# TPDH-Walrus.net
KiCad netlist of a schematic drawn in EAGLE
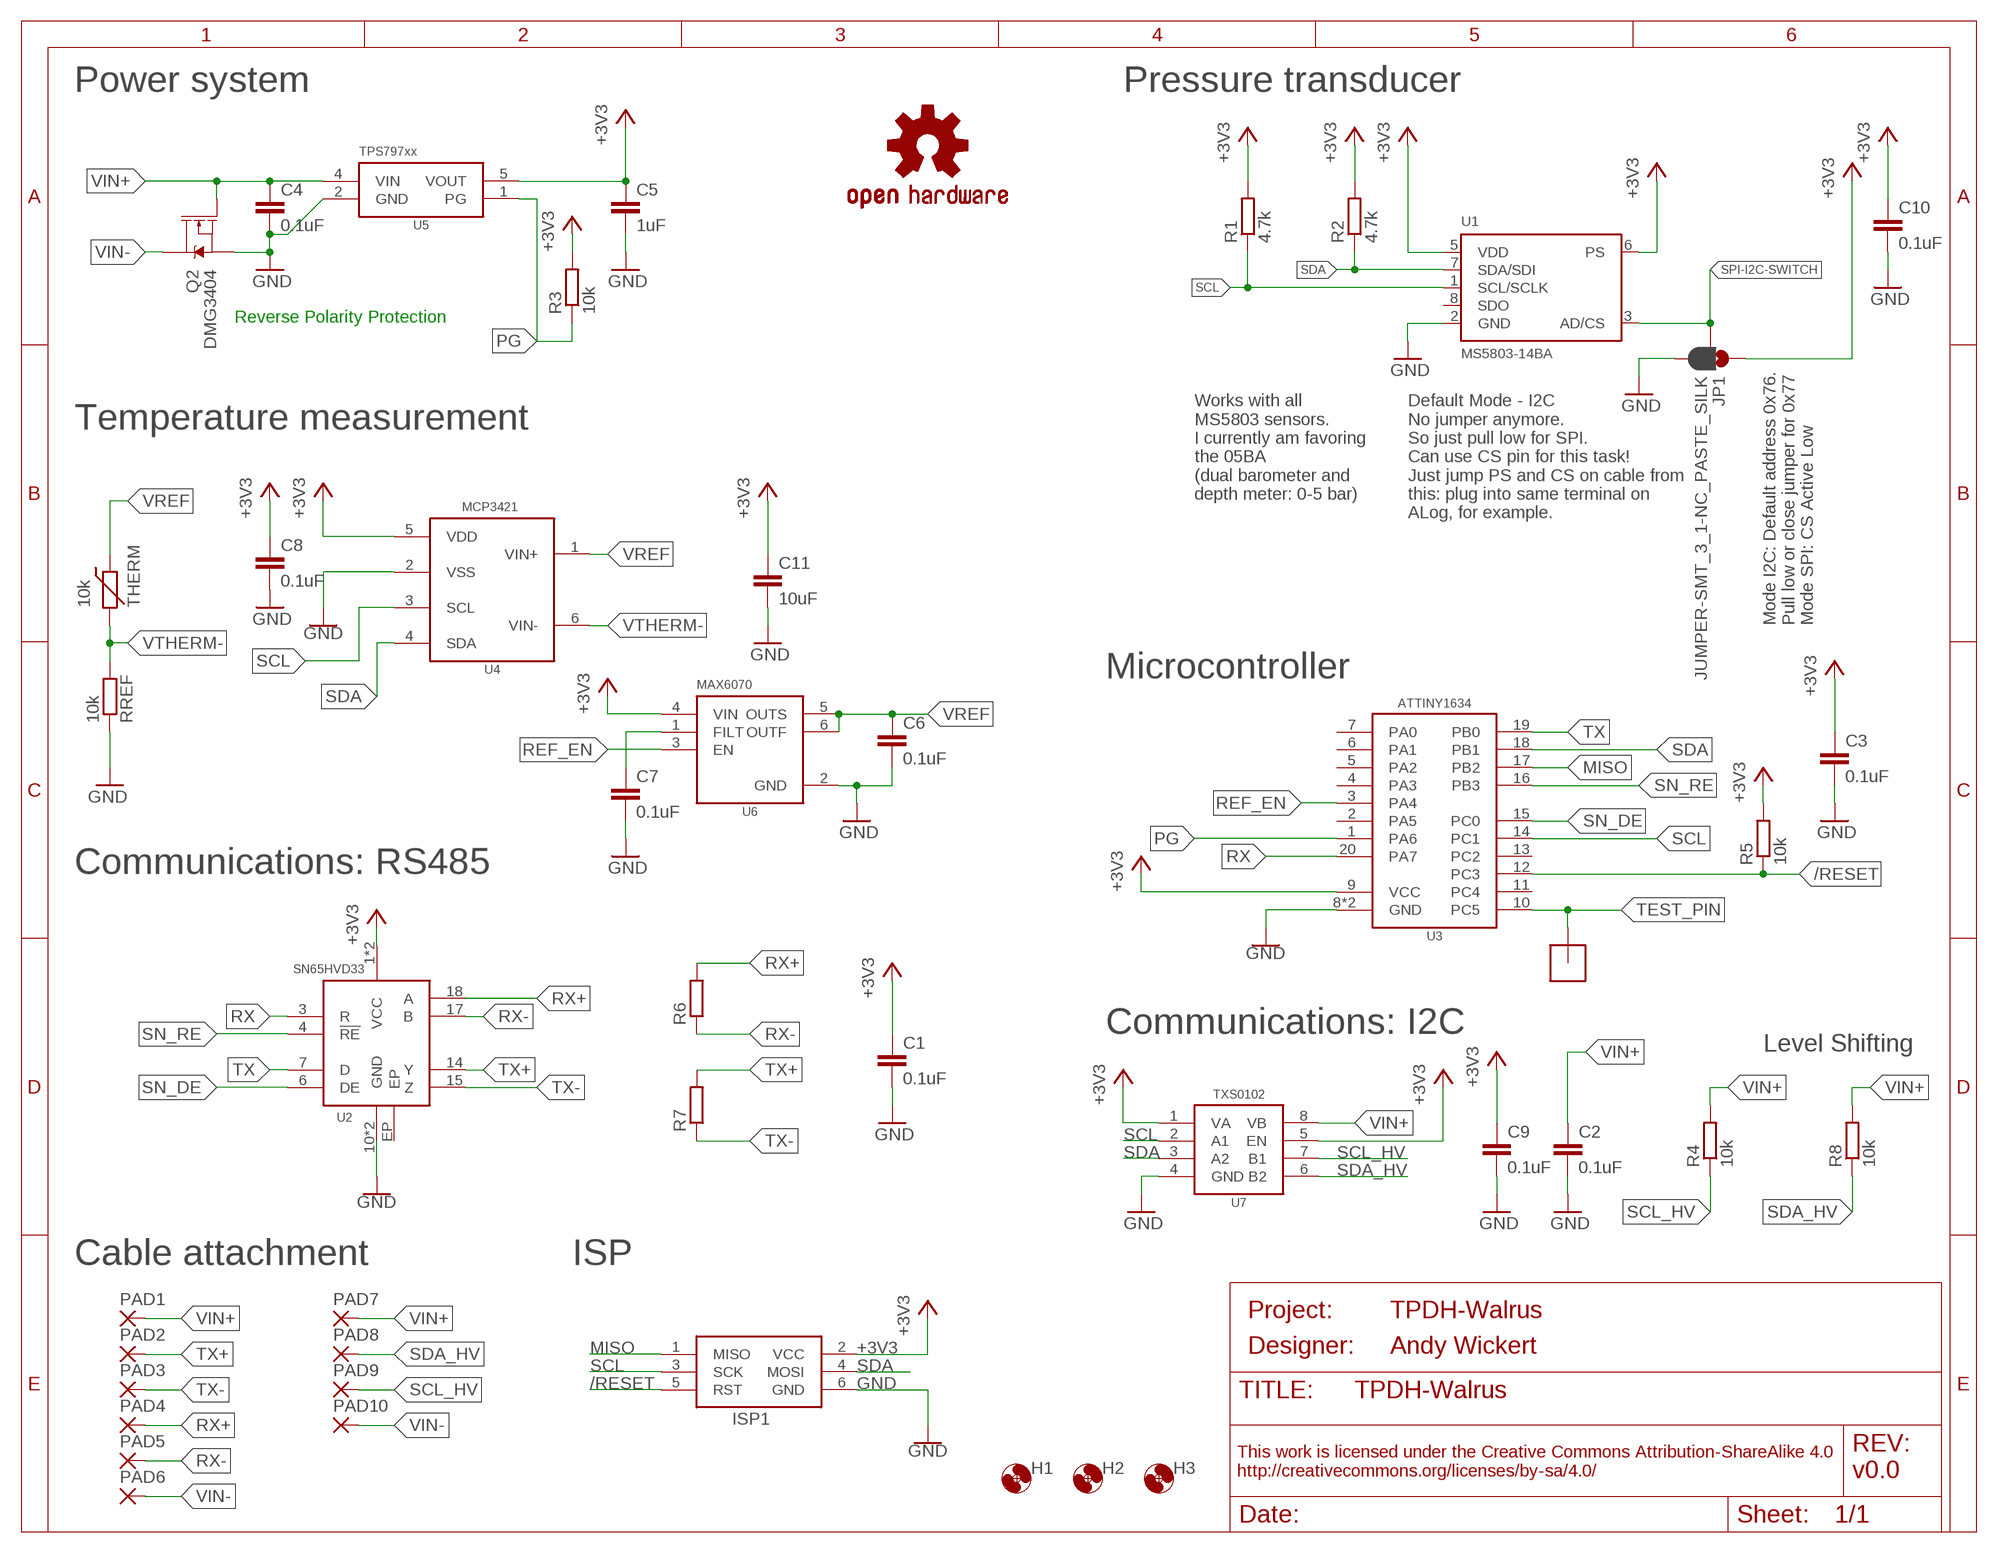
[diagram p0: schematic, sheet 1]

(export (version "E")
  (design (tool "Eeschema 10.0.6"))
  (components
    (comp (ref "C1")
      (value "0.1uF")
      (footprint "eagle-import:C0402")
      (fields (field (name "MF") "Murata") (field (name "MPN") "GCM155R71C104KA55D"))
      (libsource (lib "eagle-import") (part "C-EUC04020.1UF"))
    )
    (comp (ref "C2")
      (value "0.1uF")
      (footprint "eagle-import:C0402")
      (fields (field (name "MF") "Murata") (field (name "MPN") "GCM155R71C104KA55D"))
      (libsource (lib "eagle-import") (part "C-EUC04020.1UF"))
    )
    (comp (ref "C3")
      (value "0.1uF")
      (footprint "eagle-import:C0402")
      (fields (field (name "MF") "Murata") (field (name "MPN") "GCM155R71C104KA55D"))
      (libsource (lib "eagle-import") (part "C-EUC04020.1UF"))
    )
    (comp (ref "C4")
      (value "0.1uF")
      (footprint "eagle-import:C0402")
      (fields (field (name "MF") "Murata") (field (name "MPN") "GCM155R71C104KA55D"))
      (libsource (lib "eagle-import") (part "C-EUC04020.1UF"))
    )
    (comp (ref "C5")
      (value "1uF")
      (footprint "eagle-import:C0603")
      (fields (field (name "MF") "Murata") (field (name "MPN") "GRM188R61C105KA12D"))
      (libsource (lib "eagle-import") (part "C-EUC06031UF"))
    )
    (comp (ref "C6")
      (value "0.1uF")
      (footprint "eagle-import:C0402")
      (fields (field (name "MF") "Murata") (field (name "MPN") "GCM155R71C104KA55D"))
      (libsource (lib "eagle-import") (part "C-EUC04020.1UF"))
    )
    (comp (ref "C7")
      (value "0.1uF")
      (footprint "eagle-import:C0402")
      (fields (field (name "MF") "Murata") (field (name "MPN") "GCM155R71C104KA55D"))
      (libsource (lib "eagle-import") (part "C-EUC04020.1UF"))
    )
    (comp (ref "C8")
      (value "0.1uF")
      (footprint "eagle-import:C0402")
      (fields (field (name "MF") "Murata") (field (name "MPN") "GCM155R71C104KA55D"))
      (libsource (lib "eagle-import") (part "C-EUC04020.1UF"))
    )
    (comp (ref "C9")
      (value "0.1uF")
      (footprint "eagle-import:C0402")
      (fields (field (name "MF") "Murata") (field (name "MPN") "GCM155R71C104KA55D"))
      (libsource (lib "eagle-import") (part "C-EUC04020.1UF"))
    )
    (comp (ref "C10")
      (value "0.1uF")
      (footprint "eagle-import:C0402")
      (fields (field (name "MF") "Murata") (field (name "MPN") "GCM155R71C104KA55D"))
      (libsource (lib "eagle-import") (part "C-EUC04020.1UF"))
    )
    (comp (ref "C11")
      (value "10uF")
      (footprint "eagle-import:C0805")
      (fields (field (name "MF") "Murata") (field (name "MPN") "GRM21BR61C106KE15K"))
      (libsource (lib "eagle-import") (part "C-EUC080510UF"))
    )
    (comp (ref "H1")
      (value "MOUNTING_HOLE2_NP")
      (footprint "eagle-import:2_56")
      (libsource (lib "eagle-import") (part "MOUNTING_HOLE2_NP"))
    )
    (comp (ref "H2")
      (value "MOUNTING_HOLE2_NP")
      (footprint "eagle-import:2_56")
      (libsource (lib "eagle-import") (part "MOUNTING_HOLE2_NP"))
    )
    (comp (ref "H3")
      (value "MOUNTING_HOLE2_NP")
      (footprint "eagle-import:2_56")
      (libsource (lib "eagle-import") (part "MOUNTING_HOLE2_NP"))
    )
    (comp (ref "ISP1")
      (value "AVRISP-6")
      (footprint "eagle-import:AVRISP")
      (libsource (lib "eagle-import") (part "AVRISP-6"))
    )
    (comp (ref "JP1")
      (value "JUMPER-SMT_3_1-NC_PASTE_SILK")
      (footprint "eagle-import:SMT-JUMPER_3_1-NC_PASTE_SILK")
      (libsource (lib "eagle-import") (part "JUMPER-SMT_3_1-NC_PASTE_SILK"))
    )
    (comp (ref "LOGO1")
      (value "OSHW-LOGOM")
      (footprint "eagle-import:OSHW-LOGO-M")
      (libsource (lib "eagle-import") (part "OSHW-LOGOM"))
    )
    (comp (ref "PAD1")
      (value "2,15/1,0")
      (footprint "eagle-import:2,15_1,0")
      (libsource (lib "eagle-import") (part "2,15/1,0"))
    )
    (comp (ref "PAD2")
      (value "2,15/1,0")
      (footprint "eagle-import:2,15_1,0")
      (libsource (lib "eagle-import") (part "2,15/1,0"))
    )
    (comp (ref "PAD3")
      (value "2,15/1,0")
      (footprint "eagle-import:2,15_1,0")
      (libsource (lib "eagle-import") (part "2,15/1,0"))
    )
    (comp (ref "PAD4")
      (value "2,15/1,0")
      (footprint "eagle-import:2,15_1,0")
      (libsource (lib "eagle-import") (part "2,15/1,0"))
    )
    (comp (ref "PAD5")
      (value "2,15/1,0")
      (footprint "eagle-import:2,15_1,0")
      (libsource (lib "eagle-import") (part "2,15/1,0"))
    )
    (comp (ref "PAD6")
      (value "2,15/1,0")
      (footprint "eagle-import:2,15_1,0")
      (libsource (lib "eagle-import") (part "2,15/1,0"))
    )
    (comp (ref "PAD7")
      (value "2,15/1,0")
      (footprint "eagle-import:2,15_1,0")
      (libsource (lib "eagle-import") (part "2,15/1,0"))
    )
    (comp (ref "PAD8")
      (value "2,15/1,0")
      (footprint "eagle-import:2,15_1,0")
      (libsource (lib "eagle-import") (part "2,15/1,0"))
    )
    (comp (ref "PAD9")
      (value "2,15/1,0")
      (footprint "eagle-import:2,15_1,0")
      (libsource (lib "eagle-import") (part "2,15/1,0"))
    )
    (comp (ref "PAD10")
      (value "2,15/1,0")
      (footprint "eagle-import:2,15_1,0")
      (libsource (lib "eagle-import") (part "2,15/1,0"))
    )
    (comp (ref "Q2")
      (value "DMG3404")
      (footprint "eagle-import:SOT23-3")
      (fields (field (name "MF") "Diodes Incorporated") (field (name "MPN") "DMG3404L-7"))
      (libsource (lib "eagle-import") (part "MOSFET-NCH-DMG3404L"))
    )
    (comp (ref "R1")
      (value "4.7k")
      (footprint "eagle-import:R0402")
      (fields (field (name "MF") "Yageo") (field (name "MPN") "RC0402JR-074K7L"))
      (libsource (lib "eagle-import") (part "R-EU_R04024.7K"))
    )
    (comp (ref "R2")
      (value "4.7k")
      (footprint "eagle-import:R0402")
      (fields (field (name "MF") "Yageo") (field (name "MPN") "RC0402JR-074K7L"))
      (libsource (lib "eagle-import") (part "R-EU_R04024.7K"))
    )
    (comp (ref "R3")
      (value "10k")
      (footprint "eagle-import:R0402")
      (fields (field (name "MF") "Yageo") (field (name "MPN") "RC0603FR-0710KL"))
      (libsource (lib "eagle-import") (part "R-EU_R040210K"))
    )
    (comp (ref "R4")
      (value "10k")
      (footprint "eagle-import:R0402")
      (fields (field (name "MF") "Yageo") (field (name "MPN") "RC0603FR-0710KL"))
      (libsource (lib "eagle-import") (part "R-EU_R040210K"))
    )
    (comp (ref "R5")
      (value "10k")
      (footprint "eagle-import:R0402")
      (fields (field (name "MF") "Yageo") (field (name "MPN") "RC0603FR-0710KL"))
      (libsource (lib "eagle-import") (part "R-EU_R040210K"))
    )
    (comp (ref "R6")
      (value "R-EU_100R0402")
      (footprint "eagle-import:R0402")
      (fields
        (field (name "MF") "Yageo")
        (field (name "MPN") "RC0402FR-07100RL")
        (field (name "VALUE_PART") "100")
      )
      (libsource (lib "eagle-import") (part "R-EU_R0402100"))
    )
    (comp (ref "R7")
      (value "R-EU_100R0402")
      (footprint "eagle-import:R0402")
      (fields
        (field (name "MF") "Yageo")
        (field (name "MPN") "RC0402FR-07100RL")
        (field (name "VALUE_PART") "100")
      )
      (libsource (lib "eagle-import") (part "R-EU_R0402100"))
    )
    (comp (ref "R8")
      (value "10k")
      (footprint "eagle-import:R0402")
      (fields (field (name "MF") "Yageo") (field (name "MPN") "RC0603FR-0710KL"))
      (libsource (lib "eagle-import") (part "R-EU_R040210K"))
    )
    (comp (ref "RREF")
      (value "10k")
      (footprint "eagle-import:R0603")
      (fields
        (field (name "MF") "Panasonic")
        (field (name "MPN") "ERA-3AEB103V")
        (field (name "DIGIKEY") "P10KDBCT-ND")
        (field (name "MF_1") "Panasonic")
        (field (name "MPN_1") "ERA-3AEB103V")
      )
      (libsource (lib "eagle-import") (part "R-EU_R0603P10K"))
    )
    (comp (ref "THERM")
      (value "10k")
      (footprint "eagle-import:R0603")
      (fields
        (field (name "MF") "Murata")
        (field (name "MPN") "NCU18XH103F60RB")
        (field (name "MF_1") "Murata")
      )
      (libsource (lib "eagle-import") (part "THERMISTOR10K"))
    )
    (comp (ref "U$12")
      (value "POGO_PAD")
      (footprint "eagle-import:POGO_PAD")
      (libsource (lib "eagle-import") (part "POGO_PAD"))
    )
    (comp (ref "U1")
      (value "MS5803-14BA")
      (footprint "eagle-import:MS5803")
      (fields (field (name "MF") "TE") (field (name "MPN") "MS580305BA01-00"))
      (libsource (lib "eagle-import") (part "MS5803-14BA"))
    )
    (comp (ref "U2")
      (value "SN65HVD33RHL")
      (footprint "eagle-import:VQFN-20_POWER")
      (fields (field (name "MF") "TI") (field (name "MPN") "SN65HVD33RHLR"))
      (libsource (lib "eagle-import") (part "SN65HVD33RHL"))
    )
    (comp (ref "U3")
      (value "ATTINY1634QFN")
      (footprint "eagle-import:QFN20")
      (fields (field (name "MF") "Atmel") (field (name "MPN") "ATTINY1634-MUR"))
      (libsource (lib "eagle-import") (part "ATTINY1634QFN"))
    )
    (comp (ref "U4")
      (value "MCP3421A3")
      (footprint "eagle-import:SOT23-6L")
      (fields
        (field (name "DISP") "MCP3421")
        (field (name "MF") "Microchip")
        (field (name "MPN") "MCP3421A3T-E/CH")
      )
      (libsource (lib "eagle-import") (part "MCP3421A3"))
    )
    (comp (ref "U5")
      (value "TPS79733")
      (footprint "eagle-import:DCK_R-PDSO-G5")
      (fields (field (name "MF") "TI") (field (name "MPN") "TPS79733DCKR"))
      (libsource (lib "eagle-import") (part "TPS79733"))
    )
    (comp (ref "U6")
      (value "MAX6070AAUT18")
      (footprint "eagle-import:SOT23-6L")
      (fields (field (name "MF") "Maxim") (field (name "MPN") "MAX6070BAUT18+T"))
      (libsource (lib "eagle-import") (part "MAX6070AAUT18"))
    )
    (comp (ref "U7")
      (value "TXS0102DQM")
      (footprint "eagle-import:DQM_R-PX2SON-N8")
      (fields (field (name "MF") "TI") (field (name "MPN") "TXS0102DQMR"))
      (libsource (lib "eagle-import") (part "TXS0102DQM"))
    )
  )
  (nets
    (net (code "1") (name "+3V3") (class "Default")
      (node (ref "C1") (pin "1") (pinfunction "1_1") (pintype "passive"))
      (node (ref "C10") (pin "1") (pinfunction "1_1") (pintype "passive"))
      (node (ref "C11") (pin "1") (pinfunction "1_1") (pintype "passive"))
      (node (ref "C3") (pin "1") (pinfunction "1_1") (pintype "passive"))
      (node (ref "C5") (pin "1") (pinfunction "1_1") (pintype "passive"))
      (node (ref "C8") (pin "1") (pinfunction "1_1") (pintype "passive"))
      (node (ref "C9") (pin "1") (pinfunction "1_1") (pintype "passive"))
      (node (ref "ISP1") (pin "2") (pinfunction "VCC_2") (pintype "power_in"))
      (node (ref "JP1") (pin "1") (pinfunction "1_1") (pintype "passive"))
      (node (ref "R1") (pin "2") (pinfunction "2_2") (pintype "passive"))
      (node (ref "R2") (pin "2") (pinfunction "2_2") (pintype "passive"))
      (node (ref "R3") (pin "2") (pinfunction "2_2") (pintype "passive"))
      (node (ref "R5") (pin "2") (pinfunction "2_2") (pintype "passive"))
      (node (ref "U1") (pin "5") (pinfunction "VDD_5") (pintype "bidirectional"))
      (node (ref "U1") (pin "6") (pinfunction "PS_6") (pintype "bidirectional"))
      (node (ref "U2") (pin "1") (pinfunction "VCC_1") (pintype "power_in"))
      (node (ref "U2") (pin "20") (pinfunction "VCC_20") (pintype "power_in"))
      (node (ref "U3") (pin "9") (pinfunction "VCC_9") (pintype "power_in"))
      (node (ref "U4") (pin "5") (pinfunction "VDD_5") (pintype "passive"))
      (node (ref "U5") (pin "5") (pinfunction "VOUT_5") (pintype "bidirectional"))
      (node (ref "U6") (pin "4") (pinfunction "VIN_4") (pintype "bidirectional"))
      (node (ref "U7") (pin "1") (pinfunction "VA_1") (pintype "power_in"))
      (node (ref "U7") (pin "5") (pinfunction "EN_5") (pintype "input"))
    )
    (net (code "2") (name "GND") (class "Default")
      (node (ref "C1") (pin "2") (pinfunction "2_2") (pintype "passive"))
      (node (ref "C10") (pin "2") (pinfunction "2_2") (pintype "passive"))
      (node (ref "C11") (pin "2") (pinfunction "2_2") (pintype "passive"))
      (node (ref "C2") (pin "2") (pinfunction "2_2") (pintype "passive"))
      (node (ref "C3") (pin "2") (pinfunction "2_2") (pintype "passive"))
      (node (ref "C4") (pin "2") (pinfunction "2_2") (pintype "passive"))
      (node (ref "C5") (pin "2") (pinfunction "2_2") (pintype "passive"))
      (node (ref "C6") (pin "2") (pinfunction "2_2") (pintype "passive"))
      (node (ref "C7") (pin "2") (pinfunction "2_2") (pintype "passive"))
      (node (ref "C8") (pin "2") (pinfunction "2_2") (pintype "passive"))
      (node (ref "C9") (pin "2") (pinfunction "2_2") (pintype "passive"))
      (node (ref "ISP1") (pin "6") (pinfunction "GND_6") (pintype "power_in"))
      (node (ref "JP1") (pin "3") (pinfunction "3_3") (pintype "passive"))
      (node (ref "Q2") (pin "2") (pinfunction "S_2") (pintype "bidirectional"))
      (node (ref "RREF") (pin "1") (pinfunction "1_1") (pintype "passive"))
      (node (ref "U1") (pin "2") (pinfunction "GND_2") (pintype "bidirectional"))
      (node (ref "U2") (pin "10") (pinfunction "GND_10") (pintype "power_in"))
      (node (ref "U2") (pin "11") (pinfunction "GND_11") (pintype "power_in"))
      (node (ref "U3") (pin "8") (pinfunction "GND_8") (pintype "power_in"))
      (node (ref "U3") (pin "EP") (pinfunction "GND_EP") (pintype "power_in"))
      (node (ref "U4") (pin "2") (pinfunction "VSS_2") (pintype "passive"))
      (node (ref "U5") (pin "2") (pinfunction "GND_2") (pintype "bidirectional"))
      (node (ref "U6") (pin "2") (pinfunction "GND_2") (pintype "bidirectional"))
      (node (ref "U7") (pin "4") (pinfunction "GND_4") (pintype "power_in"))
    )
    (net (code "3") (name "MISO") (class "Default")
      (node (ref "ISP1") (pin "1") (pinfunction "MISO_1") (pintype "input"))
      (node (ref "U3") (pin "17") (pinfunction "PB2_17") (pintype "bidirectional"))
    )
    (net (code "4") (name "Net-(U6-FILT)") (class "Default")
      (node (ref "C7") (pin "1") (pinfunction "1_1") (pintype "passive"))
      (node (ref "U6") (pin "1") (pinfunction "FILT_1") (pintype "bidirectional"))
    )
    (net (code "5") (name "PG") (class "Default")
      (node (ref "R3") (pin "1") (pinfunction "1_1") (pintype "passive"))
      (node (ref "U3") (pin "1") (pinfunction "PA6_1") (pintype "bidirectional"))
      (node (ref "U5") (pin "1") (pinfunction "PG_1") (pintype "bidirectional"))
    )
    (net (code "6") (name "REF_EN") (class "Default")
      (node (ref "U3") (pin "3") (pinfunction "PA4_3") (pintype "bidirectional"))
      (node (ref "U6") (pin "3") (pinfunction "EN_3") (pintype "bidirectional"))
    )
    (net (code "7") (name "RX") (class "Default")
      (node (ref "U2") (pin "3") (pinfunction "R_3") (pintype "output"))
      (node (ref "U3") (pin "20") (pinfunction "PA7_20") (pintype "bidirectional"))
    )
    (net (code "8") (name "RX+") (class "Default")
      (node (ref "PAD4") (pin "1") (pinfunction "P_1") (pintype "passive"))
      (node (ref "R6") (pin "2") (pinfunction "2_2") (pintype "passive"))
      (node (ref "U2") (pin "18") (pinfunction "A_18") (pintype "bidirectional"))
    )
    (net (code "9") (name "RX-") (class "Default")
      (node (ref "PAD5") (pin "1") (pinfunction "P_1") (pintype "passive"))
      (node (ref "R6") (pin "1") (pinfunction "1_1") (pintype "passive"))
      (node (ref "U2") (pin "17") (pinfunction "B_17") (pintype "bidirectional"))
    )
    (net (code "10") (name "SCL") (class "Default")
      (node (ref "ISP1") (pin "3") (pinfunction "SCK_3") (pintype "output"))
      (node (ref "R1") (pin "1") (pinfunction "1_1") (pintype "passive"))
      (node (ref "U1") (pin "1") (pinfunction "SCL/SCLK_1") (pintype "bidirectional"))
      (node (ref "U3") (pin "14") (pinfunction "PC1_14") (pintype "bidirectional"))
      (node (ref "U4") (pin "3") (pinfunction "SCL_3") (pintype "bidirectional"))
      (node (ref "U7") (pin "2") (pinfunction "A1_2") (pintype "bidirectional"))
    )
    (net (code "11") (name "SCL_HV") (class "Default")
      (node (ref "PAD9") (pin "1") (pinfunction "P_1") (pintype "passive"))
      (node (ref "R4") (pin "1") (pinfunction "1_1") (pintype "passive"))
      (node (ref "U7") (pin "7") (pinfunction "B1_7") (pintype "bidirectional"))
    )
    (net (code "12") (name "SDA") (class "Default")
      (node (ref "ISP1") (pin "4") (pinfunction "MOSI_4") (pintype "output"))
      (node (ref "R2") (pin "1") (pinfunction "1_1") (pintype "passive"))
      (node (ref "U1") (pin "7") (pinfunction "SDA/SDI_7") (pintype "bidirectional"))
      (node (ref "U3") (pin "18") (pinfunction "PB1_18") (pintype "bidirectional"))
      (node (ref "U4") (pin "4") (pinfunction "SDA_4") (pintype "bidirectional"))
      (node (ref "U7") (pin "3") (pinfunction "A2_3") (pintype "bidirectional"))
    )
    (net (code "13") (name "SDA_HV") (class "Default")
      (node (ref "PAD8") (pin "1") (pinfunction "P_1") (pintype "passive"))
      (node (ref "R8") (pin "1") (pinfunction "1_1") (pintype "passive"))
      (node (ref "U7") (pin "6") (pinfunction "B2_6") (pintype "bidirectional"))
    )
    (net (code "14") (name "SN_DE") (class "Default")
      (node (ref "U2") (pin "6") (pinfunction "DE_6") (pintype "input"))
      (node (ref "U3") (pin "15") (pinfunction "PC0_15") (pintype "bidirectional"))
    )
    (net (code "15") (name "SN_RE") (class "Default")
      (node (ref "U2") (pin "4") (pinfunction "~{RE}_4") (pintype "input"))
      (node (ref "U3") (pin "16") (pinfunction "PB3_16") (pintype "bidirectional"))
    )
    (net (code "16") (name "SPI-I2C-SWITCH") (class "Default")
      (node (ref "JP1") (pin "2") (pinfunction "2_2") (pintype "passive"))
      (node (ref "U1") (pin "3") (pinfunction "AD/CS_3") (pintype "bidirectional"))
    )
    (net (code "17") (name "TEST_PIN") (class "Default")
      (node (ref "U$12") (pin "P$1") (pinfunction "P$1_P$1") (pintype "bidirectional"))
      (node (ref "U3") (pin "10") (pinfunction "PC5_10") (pintype "bidirectional"))
    )
    (net (code "18") (name "TX") (class "Default")
      (node (ref "U2") (pin "7") (pinfunction "D_7") (pintype "input"))
      (node (ref "U3") (pin "19") (pinfunction "PB0_19") (pintype "bidirectional"))
    )
    (net (code "19") (name "TX+") (class "Default")
      (node (ref "PAD2") (pin "1") (pinfunction "P_1") (pintype "passive"))
      (node (ref "R7") (pin "2") (pinfunction "2_2") (pintype "passive"))
      (node (ref "U2") (pin "14") (pinfunction "Y_14") (pintype "bidirectional"))
    )
    (net (code "20") (name "TX-") (class "Default")
      (node (ref "PAD3") (pin "1") (pinfunction "P_1") (pintype "passive"))
      (node (ref "R7") (pin "1") (pinfunction "1_1") (pintype "passive"))
      (node (ref "U2") (pin "15") (pinfunction "Z_15") (pintype "bidirectional"))
    )
    (net (code "21") (name "VIN+") (class "Default")
      (node (ref "C2") (pin "1") (pinfunction "1_1") (pintype "passive"))
      (node (ref "C4") (pin "1") (pinfunction "1_1") (pintype "passive"))
      (node (ref "PAD1") (pin "1") (pinfunction "P_1") (pintype "passive"))
      (node (ref "PAD7") (pin "1") (pinfunction "P_1") (pintype "passive"))
      (node (ref "Q2") (pin "1") (pinfunction "G_1") (pintype "bidirectional"))
      (node (ref "R4") (pin "2") (pinfunction "2_2") (pintype "passive"))
      (node (ref "R8") (pin "2") (pinfunction "2_2") (pintype "passive"))
      (node (ref "U5") (pin "4") (pinfunction "VIN_4") (pintype "bidirectional"))
      (node (ref "U7") (pin "8") (pinfunction "VB_8") (pintype "power_in"))
    )
    (net (code "22") (name "VIN-") (class "Default")
      (node (ref "PAD10") (pin "1") (pinfunction "P_1") (pintype "passive"))
      (node (ref "PAD6") (pin "1") (pinfunction "P_1") (pintype "passive"))
      (node (ref "Q2") (pin "3") (pinfunction "D_3") (pintype "bidirectional"))
    )
    (net (code "23") (name "VREF") (class "Default")
      (node (ref "C6") (pin "1") (pinfunction "1_1") (pintype "passive"))
      (node (ref "THERM") (pin "1") (pinfunction "2_1") (pintype "passive"))
      (node (ref "U4") (pin "1") (pinfunction "VIN+_1") (pintype "input"))
      (node (ref "U6") (pin "5") (pinfunction "OUTS_5") (pintype "bidirectional"))
      (node (ref "U6") (pin "6") (pinfunction "OUTF_6") (pintype "bidirectional"))
    )
    (net (code "24") (name "VTHERM-") (class "Default")
      (node (ref "RREF") (pin "2") (pinfunction "2_2") (pintype "passive"))
      (node (ref "THERM") (pin "2") (pinfunction "1_2") (pintype "passive"))
      (node (ref "U4") (pin "6") (pinfunction "VIN-_6") (pintype "input"))
    )
    (net (code "25") (name "unconnected-(U1-SDO-Pad8)") (class "Default")
      (node (ref "U1") (pin "8") (pinfunction "SDO_8") (pintype "bidirectional"))
    )
    (net (code "26") (name "unconnected-(U2-PadEP)") (class "Default")
      (node (ref "U2") (pin "EP") (pinfunction "EP_EP") (pintype "no_connect"))
    )
    (net (code "27") (name "unconnected-(U3-PA0-Pad7)") (class "Default")
      (node (ref "U3") (pin "7") (pinfunction "PA0_7") (pintype "bidirectional"))
    )
    (net (code "28") (name "unconnected-(U3-PA1-Pad6)") (class "Default")
      (node (ref "U3") (pin "6") (pinfunction "PA1_6") (pintype "bidirectional"))
    )
    (net (code "29") (name "unconnected-(U3-PA2-Pad5)") (class "Default")
      (node (ref "U3") (pin "5") (pinfunction "PA2_5") (pintype "bidirectional"))
    )
    (net (code "30") (name "unconnected-(U3-PA3-Pad4)") (class "Default")
      (node (ref "U3") (pin "4") (pinfunction "PA3_4") (pintype "bidirectional"))
    )
    (net (code "31") (name "unconnected-(U3-PA5-Pad2)") (class "Default")
      (node (ref "U3") (pin "2") (pinfunction "PA5_2") (pintype "bidirectional"))
    )
    (net (code "32") (name "unconnected-(U3-PC2-Pad13)") (class "Default")
      (node (ref "U3") (pin "13") (pinfunction "PC2_13") (pintype "bidirectional"))
    )
    (net (code "33") (name "unconnected-(U3-PC4-Pad11)") (class "Default")
      (node (ref "U3") (pin "11") (pinfunction "PC4_11") (pintype "bidirectional"))
    )
    (net (code "34") (name "{slash}RESET") (class "Default")
      (node (ref "ISP1") (pin "5") (pinfunction "RST_5") (pintype "output"))
      (node (ref "R5") (pin "1") (pinfunction "1_1") (pintype "passive"))
      (node (ref "U3") (pin "12") (pinfunction "PC3_12") (pintype "bidirectional"))
    )
  )
)
